# AT2560circuit.net
KiCad netlist of a schematic drawn in Altium Designer
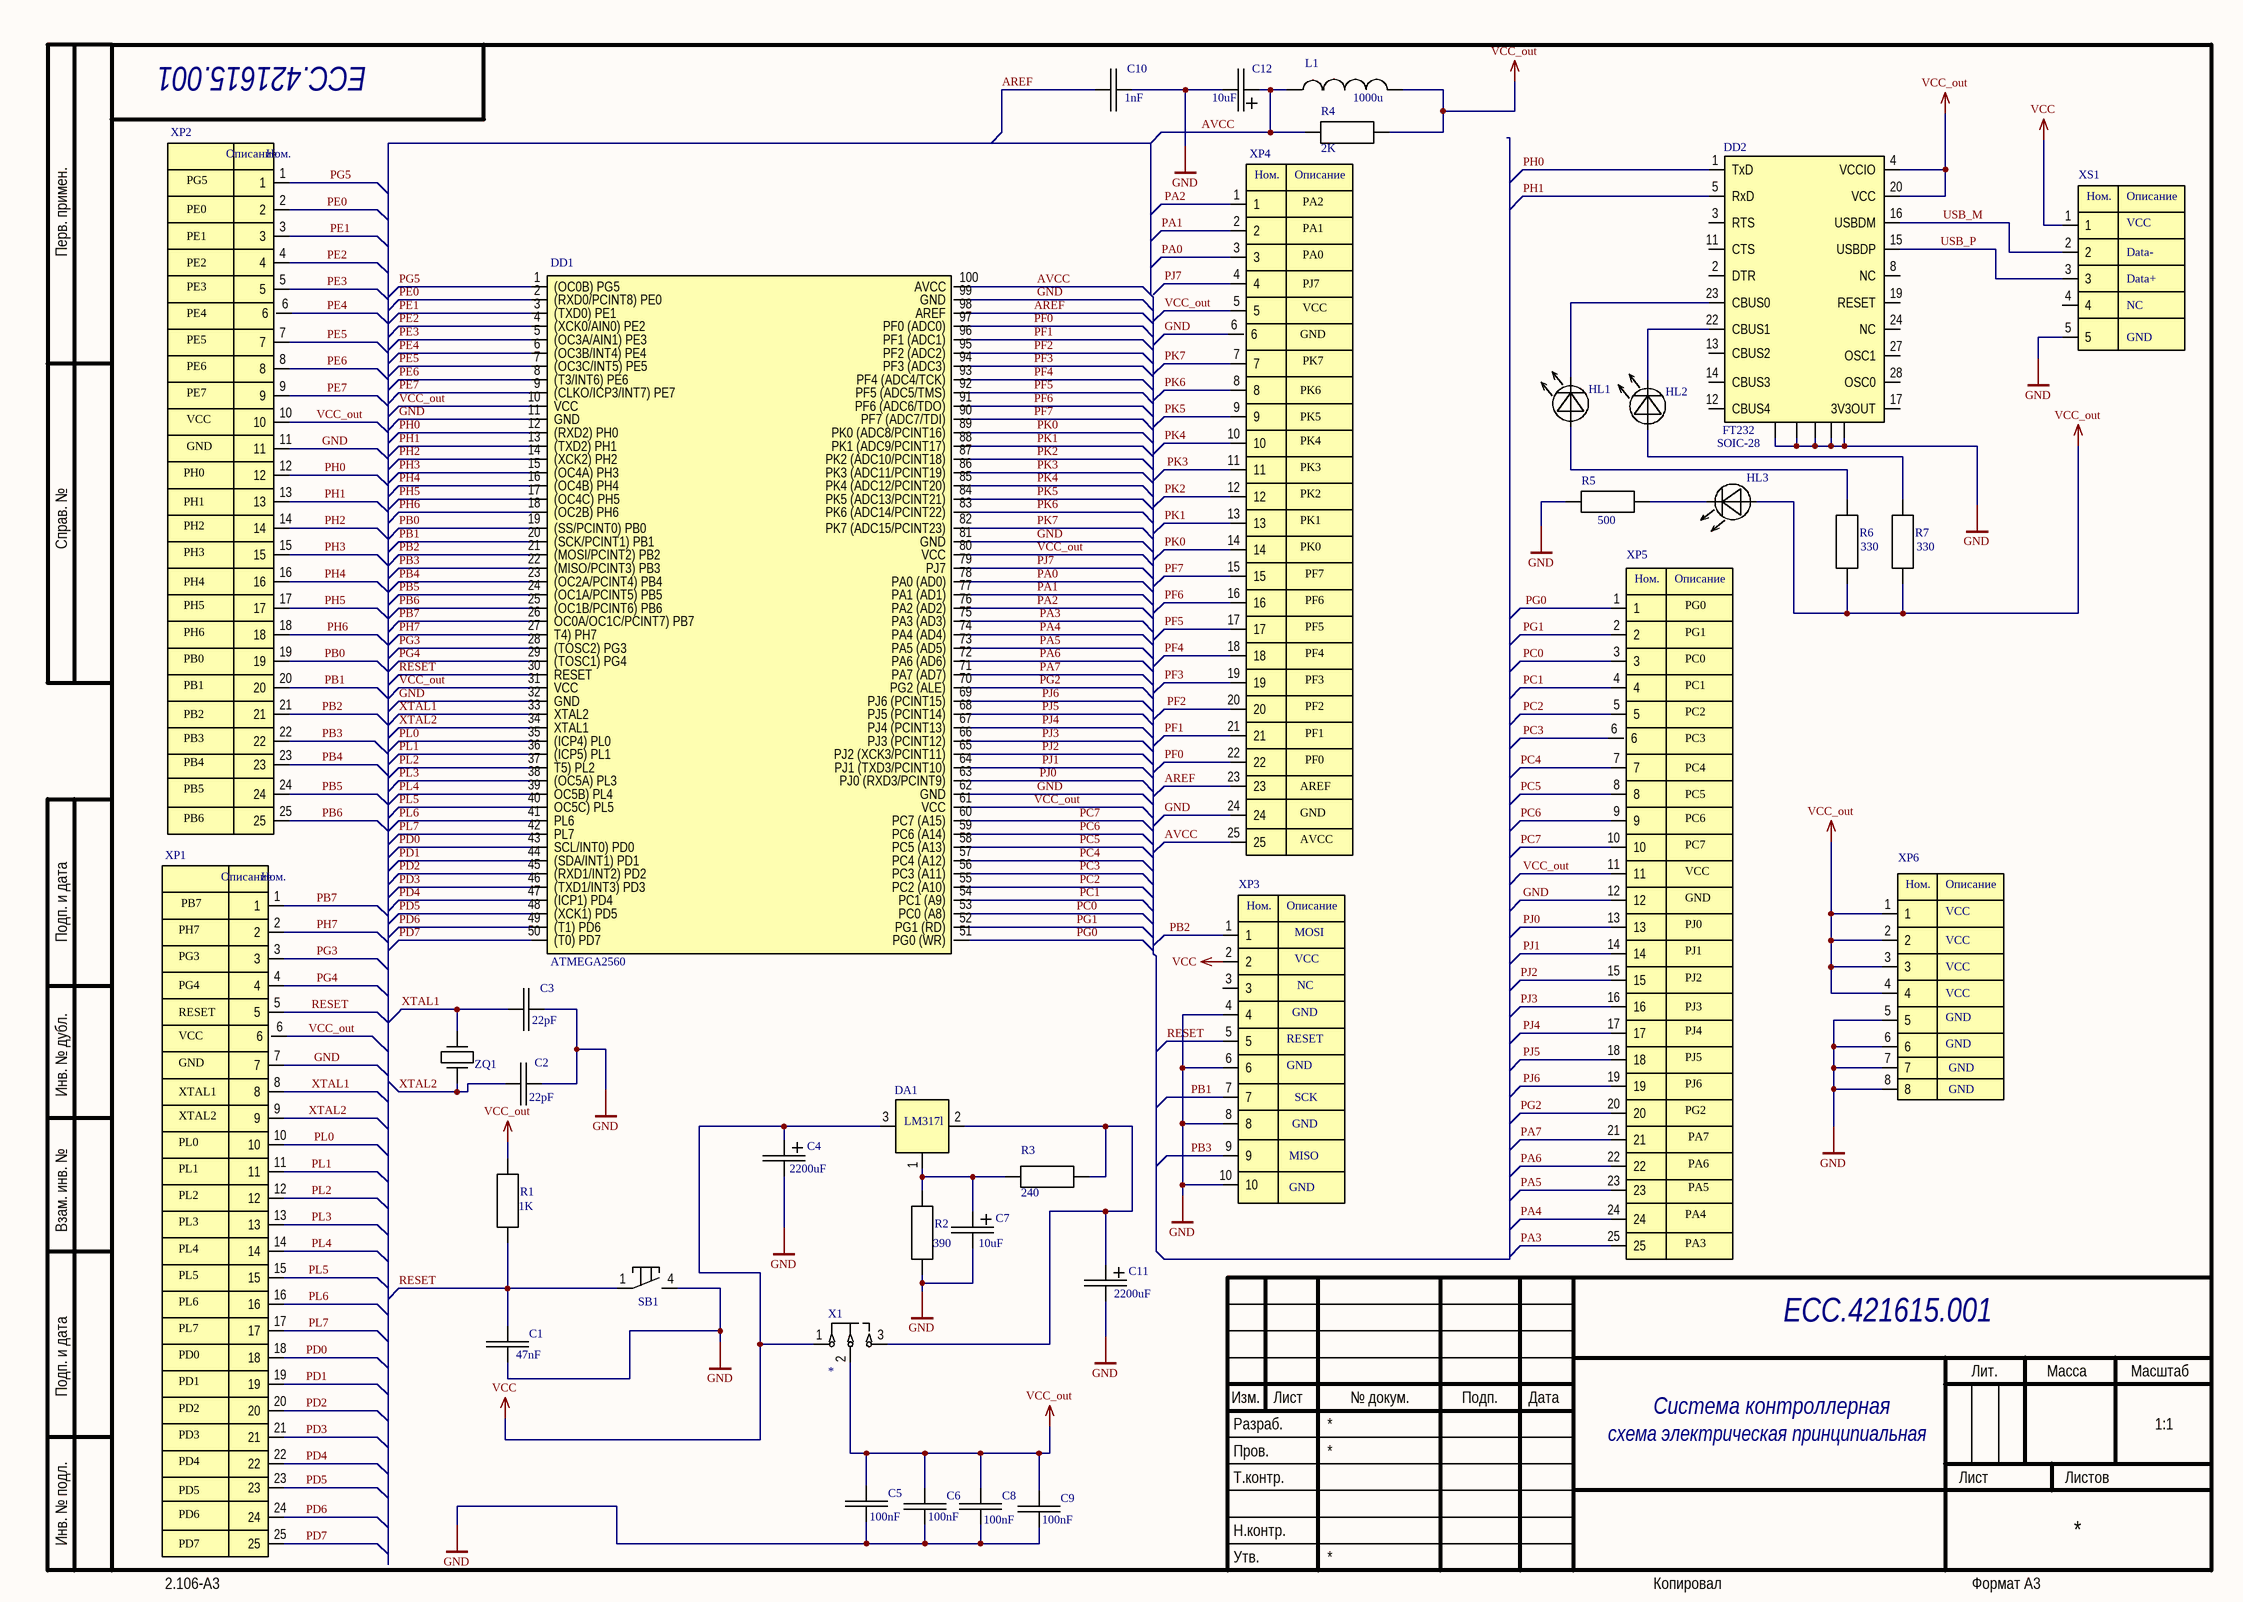
[diagram p0: AT2560circuit.SchDoc]

(export (version "E")
  (design (tool "Eeschema 10.0.6"))
  (components
    (comp (ref "C1")
      (value "Capasitor")
      (footprint "CAPC2012L")
      (fields (field (name "НОМИНАЛ") "47nF"))
      (libsource (lib "SchlibUGO") (part "Capasitor"))
    )
    (comp (ref "C2")
      (value "Capasitor")
      (footprint "CAPC2012L")
      (fields (field (name "НОМИНАЛ") "22pF"))
      (libsource (lib "SchlibUGO") (part "Capasitor"))
    )
    (comp (ref "C3")
      (value "Capasitor")
      (footprint "CAPC2012L")
      (fields (field (name "НОМИНАЛ") "22pF"))
      (libsource (lib "SchlibUGO") (part "Capasitor"))
    )
    (comp (ref "C4")
      (value "Electrolit_capasitor")
      (footprint "K50-Elect")
      (fields (field (name "НОМИНАЛ") "2200uF"))
      (libsource (lib "SchlibUGO") (part "Electrolit_capasitor"))
    )
    (comp (ref "C5")
      (value "Capasitor")
      (footprint "CAPC2012L")
      (fields (field (name "НОМИНАЛ") "100nF"))
      (libsource (lib "SchlibUGO") (part "Capasitor"))
    )
    (comp (ref "C6")
      (value "Capasitor")
      (footprint "CAPC2012L")
      (fields (field (name "НОМИНАЛ") "100nF"))
      (libsource (lib "SchlibUGO") (part "Capasitor"))
    )
    (comp (ref "C7")
      (value "Electrolit_capasitor")
      (footprint "K50-Elect")
      (fields (field (name "НОМИНАЛ") "10uF"))
      (libsource (lib "SchlibUGO") (part "Electrolit_capasitor"))
    )
    (comp (ref "C8")
      (value "Capasitor")
      (footprint "CAPC2012L")
      (fields (field (name "НОМИНАЛ") "100nF"))
      (libsource (lib "SchlibUGO") (part "Capasitor"))
    )
    (comp (ref "C9")
      (value "Capasitor")
      (footprint "CAPC2012L")
      (fields (field (name "НОМИНАЛ") "100nF"))
      (libsource (lib "SchlibUGO") (part "Capasitor"))
    )
    (comp (ref "C10")
      (value "Capasitor")
      (footprint "CAPC2012L")
      (fields (field (name "НОМИНАЛ") "1nF"))
      (libsource (lib "SchlibUGO") (part "Capasitor"))
    )
    (comp (ref "C11")
      (value "Electrolit_capasitor")
      (footprint "K50-Elect")
      (fields (field (name "НОМИНАЛ") "2200uF"))
      (libsource (lib "SchlibUGO") (part "Electrolit_capasitor"))
    )
    (comp (ref "C12")
      (value "Electrolit_capasitor")
      (footprint "K50-Elect")
      (fields (field (name "НОМИНАЛ") "10uF"))
      (libsource (lib "SchlibUGO") (part "Electrolit_capasitor"))
    )
    (comp (ref "DA1") (value "LM317l") (footprint "TO-263-3") (libsource (lib "SchlibUGO") (part "LM317l")))
    (comp (ref "DD1")
      (value "ATMega2560")
      (footprint "TSQFP50P1600X1600X120-100N")
      (fields (field (name "МАРКА") "ATMEGA2560"))
      (libsource (lib "SchlibUGO") (part "ATMega2560"))
    )
    (comp (ref "DD2")
      (value "FT232")
      (footprint "SSOP-28")
      (fields (field (name "МАРКА") "FT232") (field (name "КОРПУС") "SOIC-28"))
      (libsource (lib "SchlibUGO") (part "FT232"))
    )
    (comp (ref "HL1") (value "LED") (footprint "LED") (libsource (lib "SchlibUGO") (part "LED")))
    (comp (ref "HL2") (value "LED") (footprint "LED") (libsource (lib "SchlibUGO") (part "LED")))
    (comp (ref "HL3") (value "LED") (footprint "LED") (libsource (lib "SchlibUGO") (part "LED")))
    (comp (ref "L1")
      (value "Inductor")
      (footprint "Drossel")
      (fields (field (name "НОМИНАЛ") "1000u"))
      (libsource (lib "SchlibUGO") (part "Inductor"))
    )
    (comp (ref "R1")
      (value "Resistor")
      (footprint "RESC2012L")
      (fields (field (name "НОМИНАЛ") "1K"))
      (libsource (lib "SchlibUGO") (part "Resistor"))
    )
    (comp (ref "R2")
      (value "Resistor")
      (footprint "RESC2012L")
      (fields (field (name "НОМИНАЛ") "390"))
      (libsource (lib "SchlibUGO") (part "Resistor"))
    )
    (comp (ref "R3")
      (value "Resistor")
      (footprint "RESC2012L")
      (fields (field (name "НОМИНАЛ") "240"))
      (libsource (lib "SchlibUGO") (part "Resistor"))
    )
    (comp (ref "R4")
      (value "Resistor")
      (footprint "RESC2012L")
      (fields (field (name "НОМИНАЛ") "2K"))
      (libsource (lib "") (part "Resistor_1"))
    )
    (comp (ref "R5")
      (value "Resistor")
      (footprint "RESC2012L")
      (fields (field (name "НОМИНАЛ") "500"))
      (libsource (lib "SchlibUGO") (part "Resistor"))
    )
    (comp (ref "R6")
      (value "Resistor")
      (footprint "RESC2012L")
      (fields (field (name "НОМИНАЛ") "330"))
      (libsource (lib "SchlibUGO") (part "Resistor"))
    )
    (comp (ref "R7")
      (value "Resistor")
      (footprint "RESC2012L")
      (fields (field (name "НОМИНАЛ") "330"))
      (libsource (lib "SchlibUGO") (part "Resistor"))
    )
    (comp (ref "SB1") (value "button") (footprint "KLS2") (libsource (lib "SchlibUGO") (part "button")))
    (comp (ref "X1")
      (value "jumper")
      (footprint "PLSx3_XP")
      (fields (field (name "МАРКА") "*"))
      (libsource (lib "SchlibUGO") (part "jumper"))
    )
    (comp (ref "XP1")
      (value "Connector_plsx25")
      (footprint "PLSx25_XP")
      (libsource (lib "SchlibUGO") (part "Connector_plsx25"))
    )
    (comp (ref "XP2")
      (value "Connector_plsx25")
      (footprint "PLSx25_XP")
      (libsource (lib "") (part "Connector_plsx25_3"))
    )
    (comp (ref "XP3") (value "pls-6") (footprint "PLS6-2") (libsource (lib "SchlibUGO") (part "pls-6")))
    (comp (ref "XP4")
      (value "Connector_plsx25")
      (footprint "PLSx25_XP")
      (libsource (lib "") (part "Connector_plsx25_2"))
    )
    (comp (ref "XP5")
      (value "Connector_plsx25")
      (footprint "PLSx25_XP")
      (libsource (lib "") (part "Connector_plsx25_1"))
    )
    (comp (ref "XP6")
      (value "Power_Connector")
      (footprint "PLS-8-2")
      (libsource (lib "SchlibUGO") (part "Power_Connector"))
    )
    (comp (ref "XS1")
      (value "USB_mini_B")
      (footprint "KLS1-229-5FE")
      (libsource (lib "SchlibUGO") (part "USB_mini_B"))
    )
    (comp (ref "ZQ1") (value "Rezanator") (footprint "STS") (libsource (lib "SchlibUGO") (part "Rezanator")))
  )
  (nets
    (net (code "1") (name "/AREF") (class "Default")
      (node (ref "C10") (pin "1") (pinfunction "1_1") (pintype "passive"))
      (node (ref "DD1") (pin "98") (pinfunction "AREF_98") (pintype "passive"))
      (node (ref "XP4") (pin "23") (pinfunction "23_23") (pintype "passive"))
    )
    (net (code "2") (name "/AVCC") (class "Default")
      (node (ref "C12") (pin "1") (pinfunction "1_1") (pintype "passive"))
      (node (ref "DD1") (pin "100") (pinfunction "AVCC_100") (pintype "passive"))
      (node (ref "L1") (pin "1") (pinfunction "1_1") (pintype "passive"))
      (node (ref "R4") (pin "1") (pinfunction "1_1") (pintype "passive"))
      (node (ref "XP4") (pin "25") (pinfunction "25_25") (pintype "passive"))
    )
    (net (code "3") (name "/PA0") (class "Default")
      (node (ref "DD1") (pin "78") (pinfunction "PA0_(AD0)_78") (pintype "passive"))
      (node (ref "XP4") (pin "3") (pinfunction "3_3") (pintype "passive"))
    )
    (net (code "4") (name "/PA1") (class "Default")
      (node (ref "DD1") (pin "77") (pinfunction "PA1_(AD1)_77") (pintype "passive"))
      (node (ref "XP4") (pin "2") (pinfunction "2_2") (pintype "passive"))
    )
    (net (code "5") (name "/PA2") (class "Default")
      (node (ref "DD1") (pin "76") (pinfunction "PA2_(AD2)_76") (pintype "passive"))
      (node (ref "XP4") (pin "1") (pinfunction "1_1") (pintype "passive"))
    )
    (net (code "6") (name "/PA3") (class "Default")
      (node (ref "DD1") (pin "75") (pinfunction "PA3_(AD3)_75") (pintype "passive"))
      (node (ref "XP5") (pin "25") (pinfunction "25_25") (pintype "passive"))
    )
    (net (code "7") (name "/PA4") (class "Default")
      (node (ref "DD1") (pin "74") (pinfunction "PA4_(AD4)_74") (pintype "passive"))
      (node (ref "XP5") (pin "24") (pinfunction "24_24") (pintype "passive"))
    )
    (net (code "8") (name "/PA5") (class "Default")
      (node (ref "DD1") (pin "73") (pinfunction "PA5_(AD5)_73") (pintype "passive"))
      (node (ref "XP5") (pin "23") (pinfunction "23_23") (pintype "passive"))
    )
    (net (code "9") (name "/PA6") (class "Default")
      (node (ref "DD1") (pin "72") (pinfunction "PA6_(AD6)_72") (pintype "passive"))
      (node (ref "XP5") (pin "22") (pinfunction "22_22") (pintype "passive"))
    )
    (net (code "10") (name "/PA7") (class "Default")
      (node (ref "DD1") (pin "71") (pinfunction "PA7_(AD7)_71") (pintype "passive"))
      (node (ref "XP5") (pin "21") (pinfunction "21_21") (pintype "passive"))
    )
    (net (code "11") (name "/PB0") (class "Default")
      (node (ref "DD1") (pin "19") (pinfunction "(SS/PCINT0)_PB0_19") (pintype "passive"))
      (node (ref "XP2") (pin "19") (pinfunction "19_19") (pintype "passive"))
    )
    (net (code "12") (name "/PB1") (class "Default")
      (node (ref "DD1") (pin "20") (pinfunction "(SCK/PCINT1)_PB1_20") (pintype "passive"))
      (node (ref "XP2") (pin "20") (pinfunction "20_20") (pintype "passive"))
      (node (ref "XP3") (pin "7") (pinfunction "7_7") (pintype "passive"))
    )
    (net (code "13") (name "/PB2") (class "Default")
      (node (ref "DD1") (pin "21") (pinfunction "(MOSI/PCINT2)_PB2_21") (pintype "passive"))
      (node (ref "XP2") (pin "21") (pinfunction "21_21") (pintype "passive"))
      (node (ref "XP3") (pin "1") (pinfunction "1_1") (pintype "passive"))
    )
    (net (code "14") (name "/PB3") (class "Default")
      (node (ref "DD1") (pin "22") (pinfunction "(MISO/PCINT3)_PB3_22") (pintype "passive"))
      (node (ref "XP2") (pin "22") (pinfunction "22_22") (pintype "passive"))
      (node (ref "XP3") (pin "9") (pinfunction "9_9") (pintype "passive"))
    )
    (net (code "15") (name "/PB4") (class "Default")
      (node (ref "DD1") (pin "23") (pinfunction "(OC2A/PCINT4)_PB4_23") (pintype "passive"))
      (node (ref "XP2") (pin "23") (pinfunction "23_23") (pintype "passive"))
    )
    (net (code "16") (name "/PB5") (class "Default")
      (node (ref "DD1") (pin "24") (pinfunction "(OC1A/PCINT5)_PB5_24") (pintype "passive"))
      (node (ref "XP2") (pin "24") (pinfunction "24_24") (pintype "passive"))
    )
    (net (code "17") (name "/PB6") (class "Default")
      (node (ref "DD1") (pin "25") (pinfunction "(OC1B/PCINT6)_PB6_25") (pintype "passive"))
      (node (ref "XP2") (pin "25") (pinfunction "25_25") (pintype "passive"))
    )
    (net (code "18") (name "/PB7") (class "Default")
      (node (ref "DD1") (pin "26") (pinfunction "OC0A/OC1C/PCINT7)_PB7_26") (pintype "passive"))
      (node (ref "XP1") (pin "1") (pinfunction "1_1") (pintype "passive"))
    )
    (net (code "19") (name "/PC0") (class "Default")
      (node (ref "DD1") (pin "53") (pinfunction "PC0_(A8)_53") (pintype "passive"))
      (node (ref "XP5") (pin "3") (pinfunction "3_3") (pintype "passive"))
    )
    (net (code "20") (name "/PC1") (class "Default")
      (node (ref "DD1") (pin "54") (pinfunction "PC1_(A9)_54") (pintype "passive"))
      (node (ref "XP5") (pin "4") (pinfunction "4_4") (pintype "passive"))
    )
    (net (code "21") (name "/PC2") (class "Default")
      (node (ref "DD1") (pin "55") (pinfunction "PC2_(A10)_55") (pintype "passive"))
      (node (ref "XP5") (pin "5") (pinfunction "5_5") (pintype "passive"))
    )
    (net (code "22") (name "/PC3") (class "Default")
      (node (ref "DD1") (pin "56") (pinfunction "PC3_(A11)_56") (pintype "passive"))
      (node (ref "XP5") (pin "6") (pinfunction "6_6") (pintype "passive"))
    )
    (net (code "23") (name "/PC4") (class "Default")
      (node (ref "DD1") (pin "57") (pinfunction "PC4_(A12)_57") (pintype "passive"))
      (node (ref "XP5") (pin "7") (pinfunction "7_7") (pintype "passive"))
    )
    (net (code "24") (name "/PC5") (class "Default")
      (node (ref "DD1") (pin "58") (pinfunction "PC5_(A13)_58") (pintype "passive"))
      (node (ref "XP5") (pin "8") (pinfunction "8_8") (pintype "passive"))
    )
    (net (code "25") (name "/PC6") (class "Default")
      (node (ref "DD1") (pin "59") (pinfunction "PC6_(A14)_59") (pintype "passive"))
      (node (ref "XP5") (pin "9") (pinfunction "9_9") (pintype "passive"))
    )
    (net (code "26") (name "/PC7") (class "Default")
      (node (ref "DD1") (pin "60") (pinfunction "PC7_(A15)_60") (pintype "passive"))
      (node (ref "XP5") (pin "10") (pinfunction "10_10") (pintype "passive"))
    )
    (net (code "27") (name "/PD0") (class "Default")
      (node (ref "DD1") (pin "43") (pinfunction "SCL/INT0)_PD0_43") (pintype "passive"))
      (node (ref "XP1") (pin "18") (pinfunction "18_18") (pintype "passive"))
    )
    (net (code "28") (name "/PD1") (class "Default")
      (node (ref "DD1") (pin "44") (pinfunction "(SDA/INT1)_PD1_44") (pintype "passive"))
      (node (ref "XP1") (pin "19") (pinfunction "19_19") (pintype "passive"))
    )
    (net (code "29") (name "/PD2") (class "Default")
      (node (ref "DD1") (pin "45") (pinfunction "(RXD1/INT2)_PD2_45") (pintype "passive"))
      (node (ref "XP1") (pin "20") (pinfunction "20_20") (pintype "passive"))
    )
    (net (code "30") (name "/PD3") (class "Default")
      (node (ref "DD1") (pin "46") (pinfunction "(TXD1/INT3)_PD3_46") (pintype "passive"))
      (node (ref "XP1") (pin "21") (pinfunction "21_21") (pintype "passive"))
    )
    (net (code "31") (name "/PD4") (class "Default")
      (node (ref "DD1") (pin "47") (pinfunction "(ICP1)_PD4_47") (pintype "passive"))
      (node (ref "XP1") (pin "22") (pinfunction "22_22") (pintype "passive"))
    )
    (net (code "32") (name "/PD5") (class "Default")
      (node (ref "DD1") (pin "48") (pinfunction "(XCK1)_PD5_48") (pintype "passive"))
      (node (ref "XP1") (pin "23") (pinfunction "23_23") (pintype "passive"))
    )
    (net (code "33") (name "/PD6") (class "Default")
      (node (ref "DD1") (pin "49") (pinfunction "(T1)_PD6_49") (pintype "passive"))
      (node (ref "XP1") (pin "24") (pinfunction "24_24") (pintype "passive"))
    )
    (net (code "34") (name "/PD7") (class "Default")
      (node (ref "DD1") (pin "50") (pinfunction "(T0)_PD7_50") (pintype "passive"))
      (node (ref "XP1") (pin "25") (pinfunction "25_25") (pintype "passive"))
    )
    (net (code "35") (name "/PE0") (class "Default")
      (node (ref "DD1") (pin "2") (pinfunction "(RXD0/PCINT8)_PE0_2") (pintype "passive"))
      (node (ref "XP2") (pin "2") (pinfunction "2_2") (pintype "passive"))
    )
    (net (code "36") (name "/PE1") (class "Default")
      (node (ref "DD1") (pin "3") (pinfunction "(TXD0)_PE1_3") (pintype "passive"))
      (node (ref "XP2") (pin "3") (pinfunction "3_3") (pintype "passive"))
    )
    (net (code "37") (name "/PE2") (class "Default")
      (node (ref "DD1") (pin "4") (pinfunction "(XCK0/AIN0)_PE2_4") (pintype "passive"))
      (node (ref "XP2") (pin "4") (pinfunction "4_4") (pintype "passive"))
    )
    (net (code "38") (name "/PE3") (class "Default")
      (node (ref "DD1") (pin "5") (pinfunction "(OC3A/AIN1)_PE3_5") (pintype "passive"))
      (node (ref "XP2") (pin "5") (pinfunction "5_5") (pintype "passive"))
    )
    (net (code "39") (name "/PE4") (class "Default")
      (node (ref "DD1") (pin "6") (pinfunction "(OC3B/INT4)_PE4_6") (pintype "passive"))
      (node (ref "XP2") (pin "6") (pinfunction "6_6") (pintype "passive"))
    )
    (net (code "40") (name "/PE5") (class "Default")
      (node (ref "DD1") (pin "7") (pinfunction "(OC3C/INT5)_PE5_7") (pintype "passive"))
      (node (ref "XP2") (pin "7") (pinfunction "7_7") (pintype "passive"))
    )
    (net (code "41") (name "/PE6") (class "Default")
      (node (ref "DD1") (pin "8") (pinfunction "(T3/INT6)_PE6_8") (pintype "passive"))
      (node (ref "XP2") (pin "8") (pinfunction "8_8") (pintype "passive"))
    )
    (net (code "42") (name "/PE7") (class "Default")
      (node (ref "DD1") (pin "9") (pinfunction "(CLKO/ICP3/INT7)_PE7_9") (pintype "passive"))
      (node (ref "XP2") (pin "9") (pinfunction "9_9") (pintype "passive"))
    )
    (net (code "43") (name "/PF0") (class "Default")
      (node (ref "DD1") (pin "97") (pinfunction "PF0_(ADC0)_97") (pintype "passive"))
      (node (ref "XP4") (pin "22") (pinfunction "22_22") (pintype "passive"))
    )
    (net (code "44") (name "/PF1") (class "Default")
      (node (ref "DD1") (pin "96") (pinfunction "PF1_(ADC1)_96") (pintype "passive"))
      (node (ref "XP4") (pin "21") (pinfunction "21_21") (pintype "passive"))
    )
    (net (code "45") (name "/PF2") (class "Default")
      (node (ref "DD1") (pin "95") (pinfunction "PF2_(ADC2)_95") (pintype "passive"))
      (node (ref "XP4") (pin "20") (pinfunction "20_20") (pintype "passive"))
    )
    (net (code "46") (name "/PF3") (class "Default")
      (node (ref "DD1") (pin "94") (pinfunction "PF3_(ADC3)_94") (pintype "passive"))
      (node (ref "XP4") (pin "19") (pinfunction "19_19") (pintype "passive"))
    )
    (net (code "47") (name "/PF4") (class "Default")
      (node (ref "DD1") (pin "93") (pinfunction "PF4_(ADC4/TCK)_93") (pintype "passive"))
      (node (ref "XP4") (pin "18") (pinfunction "18_18") (pintype "passive"))
    )
    (net (code "48") (name "/PF5") (class "Default")
      (node (ref "DD1") (pin "92") (pinfunction "PF5_(ADC5/TMS)_92") (pintype "passive"))
      (node (ref "XP4") (pin "17") (pinfunction "17_17") (pintype "passive"))
    )
    (net (code "49") (name "/PF6") (class "Default")
      (node (ref "DD1") (pin "91") (pinfunction "PF6_(ADC6/TDO)_91") (pintype "passive"))
      (node (ref "XP4") (pin "16") (pinfunction "16_16") (pintype "passive"))
    )
    (net (code "50") (name "/PF7") (class "Default")
      (node (ref "DD1") (pin "90") (pinfunction "PF7_(ADC7/TDI)_90") (pintype "passive"))
      (node (ref "XP4") (pin "15") (pinfunction "15_15") (pintype "passive"))
    )
    (net (code "51") (name "/PG0") (class "Default")
      (node (ref "DD1") (pin "51") (pinfunction "PG0_(WR)_51") (pintype "passive"))
      (node (ref "XP5") (pin "1") (pinfunction "1_1") (pintype "passive"))
    )
    (net (code "52") (name "/PG1") (class "Default")
      (node (ref "DD1") (pin "52") (pinfunction "PG1_(RD)_52") (pintype "passive"))
      (node (ref "XP5") (pin "2") (pinfunction "2_2") (pintype "passive"))
    )
    (net (code "53") (name "/PG2") (class "Default")
      (node (ref "DD1") (pin "70") (pinfunction "PG2_(ALE)_70") (pintype "passive"))
      (node (ref "XP5") (pin "20") (pinfunction "20_20") (pintype "passive"))
    )
    (net (code "54") (name "/PG3") (class "Default")
      (node (ref "DD1") (pin "28") (pinfunction "(TOSC2)_PG3_28") (pintype "passive"))
      (node (ref "XP1") (pin "3") (pinfunction "3_3") (pintype "passive"))
    )
    (net (code "55") (name "/PG4") (class "Default")
      (node (ref "DD1") (pin "29") (pinfunction "(TOSC1)_PG4_29") (pintype "passive"))
      (node (ref "XP1") (pin "4") (pinfunction "4_4") (pintype "passive"))
    )
    (net (code "56") (name "/PG5") (class "Default")
      (node (ref "DD1") (pin "1") (pinfunction "(OC0B)_PG5_1") (pintype "passive"))
      (node (ref "XP2") (pin "1") (pinfunction "1_1") (pintype "passive"))
    )
    (net (code "57") (name "/PH0") (class "Default")
      (node (ref "DD1") (pin "12") (pinfunction "(RXD2)_PH0_12") (pintype "passive"))
      (node (ref "DD2") (pin "1") (pinfunction "TxD_1") (pintype "passive"))
      (node (ref "XP2") (pin "12") (pinfunction "12_12") (pintype "passive"))
    )
    (net (code "58") (name "/PH1") (class "Default")
      (node (ref "DD1") (pin "13") (pinfunction "(TXD2)_PH1_13") (pintype "passive"))
      (node (ref "DD2") (pin "5") (pinfunction "RxD_5") (pintype "passive"))
      (node (ref "XP2") (pin "13") (pinfunction "13_13") (pintype "passive"))
    )
    (net (code "59") (name "/PH2") (class "Default")
      (node (ref "DD1") (pin "14") (pinfunction "(XCK2)_PH2_14") (pintype "passive"))
      (node (ref "XP2") (pin "14") (pinfunction "14_14") (pintype "passive"))
    )
    (net (code "60") (name "/PH3") (class "Default")
      (node (ref "DD1") (pin "15") (pinfunction "(OC4A)_PH3_15") (pintype "passive"))
      (node (ref "XP2") (pin "15") (pinfunction "15_15") (pintype "passive"))
    )
    (net (code "61") (name "/PH4") (class "Default")
      (node (ref "DD1") (pin "16") (pinfunction "(OC4B)_PH4_16") (pintype "passive"))
      (node (ref "XP2") (pin "16") (pinfunction "16_16") (pintype "passive"))
    )
    (net (code "62") (name "/PH5") (class "Default")
      (node (ref "DD1") (pin "17") (pinfunction "(OC4C)_PH5_17") (pintype "passive"))
      (node (ref "XP2") (pin "17") (pinfunction "17_17") (pintype "passive"))
    )
    (net (code "63") (name "/PH6") (class "Default")
      (node (ref "DD1") (pin "18") (pinfunction "(OC2B)_PH6_18") (pintype "passive"))
      (node (ref "XP2") (pin "18") (pinfunction "18_18") (pintype "passive"))
    )
    (net (code "64") (name "/PH7") (class "Default")
      (node (ref "DD1") (pin "27") (pinfunction "T4)_PH7_27") (pintype "passive"))
      (node (ref "XP1") (pin "2") (pinfunction "2_2") (pintype "passive"))
    )
    (net (code "65") (name "/PJ0") (class "Default")
      (node (ref "DD1") (pin "63") (pinfunction "PJ0_(RXD3/PCINT9)_63") (pintype "passive"))
      (node (ref "XP5") (pin "13") (pinfunction "13_13") (pintype "passive"))
    )
    (net (code "66") (name "/PJ1") (class "Default")
      (node (ref "DD1") (pin "64") (pinfunction "PJ1_(TXD3/PCINT10)_64") (pintype "passive"))
      (node (ref "XP5") (pin "14") (pinfunction "14_14") (pintype "passive"))
    )
    (net (code "67") (name "/PJ2") (class "Default")
      (node (ref "DD1") (pin "65") (pinfunction "PJ2_(XCK3/PCINT11)_65") (pintype "passive"))
      (node (ref "XP5") (pin "15") (pinfunction "15_15") (pintype "passive"))
    )
    (net (code "68") (name "/PJ3") (class "Default")
      (node (ref "DD1") (pin "66") (pinfunction "PJ3_(PCINT12)_66") (pintype "passive"))
      (node (ref "XP5") (pin "16") (pinfunction "16_16") (pintype "passive"))
    )
    (net (code "69") (name "/PJ4") (class "Default")
      (node (ref "DD1") (pin "67") (pinfunction "PJ4_(PCINT13)_67") (pintype "passive"))
      (node (ref "XP5") (pin "17") (pinfunction "17_17") (pintype "passive"))
    )
    (net (code "70") (name "/PJ5") (class "Default")
      (node (ref "DD1") (pin "68") (pinfunction "PJ5_(PCINT14)_68") (pintype "passive"))
      (node (ref "XP5") (pin "18") (pinfunction "18_18") (pintype "passive"))
    )
    (net (code "71") (name "/PJ6") (class "Default")
      (node (ref "DD1") (pin "69") (pinfunction "PJ6_(PCINT15)_69") (pintype "passive"))
      (node (ref "XP5") (pin "19") (pinfunction "19_19") (pintype "passive"))
    )
    (net (code "72") (name "/PJ7") (class "Default")
      (node (ref "DD1") (pin "79") (pinfunction "PJ7_79") (pintype "passive"))
      (node (ref "XP4") (pin "4") (pinfunction "4_4") (pintype "passive"))
    )
    (net (code "73") (name "/PK0") (class "Default")
      (node (ref "DD1") (pin "89") (pinfunction "PK0_(ADC8/PCINT16)_89") (pintype "passive"))
      (node (ref "XP4") (pin "14") (pinfunction "14_14") (pintype "passive"))
    )
    (net (code "74") (name "/PK1") (class "Default")
      (node (ref "DD1") (pin "88") (pinfunction "PK1_(ADC9/PCINT17)_88") (pintype "passive"))
      (node (ref "XP4") (pin "13") (pinfunction "13_13") (pintype "passive"))
    )
    (net (code "75") (name "/PK2") (class "Default")
      (node (ref "DD1") (pin "87") (pinfunction "PK2_(ADC10/PCINT18)_87") (pintype "passive"))
      (node (ref "XP4") (pin "12") (pinfunction "12_12") (pintype "passive"))
    )
    (net (code "76") (name "/PK3") (class "Default")
      (node (ref "DD1") (pin "86") (pinfunction "PK3_(ADC11/PCINT19)_86") (pintype "passive"))
      (node (ref "XP4") (pin "11") (pinfunction "11_11") (pintype "passive"))
    )
    (net (code "77") (name "/PK4") (class "Default")
      (node (ref "DD1") (pin "85") (pinfunction "PK4_(ADC12/PCINT20)_85") (pintype "passive"))
      (node (ref "XP4") (pin "10") (pinfunction "10_10") (pintype "passive"))
    )
    (net (code "78") (name "/PK5") (class "Default")
      (node (ref "DD1") (pin "84") (pinfunction "PK5_(ADC13/PCINT21)_84") (pintype "passive"))
      (node (ref "XP4") (pin "9") (pinfunction "9_9") (pintype "passive"))
    )
    (net (code "79") (name "/PK6") (class "Default")
      (node (ref "DD1") (pin "83") (pinfunction "PK6_(ADC14/PCINT22)_83") (pintype "passive"))
      (node (ref "XP4") (pin "8") (pinfunction "8_8") (pintype "passive"))
    )
    (net (code "80") (name "/PK7") (class "Default")
      (node (ref "DD1") (pin "82") (pinfunction "PK7_(ADC15/PCINT23)_82") (pintype "passive"))
      (node (ref "XP4") (pin "7") (pinfunction "7_7") (pintype "passive"))
    )
    (net (code "81") (name "/PL0") (class "Default")
      (node (ref "DD1") (pin "35") (pinfunction "(ICP4)_PL0_35") (pintype "passive"))
      (node (ref "XP1") (pin "10") (pinfunction "10_10") (pintype "passive"))
    )
    (net (code "82") (name "/PL1") (class "Default")
      (node (ref "DD1") (pin "36") (pinfunction "(ICP5)_PL1_36") (pintype "passive"))
      (node (ref "XP1") (pin "11") (pinfunction "11_11") (pintype "passive"))
    )
    (net (code "83") (name "/PL2") (class "Default")
      (node (ref "DD1") (pin "37") (pinfunction "T5)_PL2_37") (pintype "passive"))
      (node (ref "XP1") (pin "12") (pinfunction "12_12") (pintype "passive"))
    )
    (net (code "84") (name "/PL3") (class "Default")
      (node (ref "DD1") (pin "38") (pinfunction "(OC5A)_PL3_38") (pintype "passive"))
      (node (ref "XP1") (pin "13") (pinfunction "13_13") (pintype "passive"))
    )
    (net (code "85") (name "/PL4") (class "Default")
      (node (ref "DD1") (pin "39") (pinfunction "OC5B)_PL4_39") (pintype "passive"))
      (node (ref "XP1") (pin "14") (pinfunction "14_14") (pintype "passive"))
    )
    (net (code "86") (name "/PL5") (class "Default")
      (node (ref "DD1") (pin "40") (pinfunction "OC5C)_PL5_40") (pintype "passive"))
      (node (ref "XP1") (pin "15") (pinfunction "15_15") (pintype "passive"))
    )
    (net (code "87") (name "/PL6") (class "Default")
      (node (ref "DD1") (pin "41") (pinfunction "PL6_41") (pintype "passive"))
      (node (ref "XP1") (pin "16") (pinfunction "16_16") (pintype "passive"))
    )
    (net (code "88") (name "/PL7") (class "Default")
      (node (ref "DD1") (pin "42") (pinfunction "PL7_42") (pintype "passive"))
      (node (ref "XP1") (pin "17") (pinfunction "17_17") (pintype "passive"))
    )
    (net (code "89") (name "/RESET") (class "Default")
      (node (ref "C1") (pin "1") (pinfunction "1_1") (pintype "passive"))
      (node (ref "DD1") (pin "30") (pinfunction "RESET_30") (pintype "passive"))
      (node (ref "R1") (pin "1") (pinfunction "1_1") (pintype "passive"))
      (node (ref "SB1") (pin "1") (pinfunction "1_1") (pintype "passive"))
      (node (ref "XP1") (pin "5") (pinfunction "5_5") (pintype "passive"))
      (node (ref "XP3") (pin "5") (pinfunction "5_5") (pintype "passive"))
    )
    (net (code "90") (name "/USB_M") (class "Default")
      (node (ref "DD2") (pin "16") (pinfunction "USBDM_16") (pintype "passive"))
      (node (ref "XS1") (pin "2") (pinfunction "2_2") (pintype "passive"))
    )
    (net (code "91") (name "/USB_P") (class "Default")
      (node (ref "DD2") (pin "15") (pinfunction "USBDP_15") (pintype "passive"))
      (node (ref "XS1") (pin "3") (pinfunction "3_3") (pintype "passive"))
    )
    (net (code "92") (name "/XTAL1") (class "Default")
      (node (ref "C3") (pin "2") (pinfunction "2_2") (pintype "passive"))
      (node (ref "DD1") (pin "33") (pinfunction "XTAL2_33") (pintype "passive"))
      (node (ref "XP1") (pin "8") (pinfunction "8_8") (pintype "passive"))
      (node (ref "ZQ1") (pin "2") (pinfunction "2_2") (pintype "passive"))
    )
    (net (code "93") (name "/XTAL2") (class "Default")
      (node (ref "C2") (pin "2") (pinfunction "2_2") (pintype "passive"))
      (node (ref "DD1") (pin "34") (pinfunction "XTAL1_34") (pintype "passive"))
      (node (ref "XP1") (pin "9") (pinfunction "9_9") (pintype "passive"))
      (node (ref "ZQ1") (pin "1") (pinfunction "1_1") (pintype "passive"))
    )
    (net (code "94") (name "GND") (class "Default")
      (node (ref "C1") (pin "2") (pinfunction "2_2") (pintype "passive"))
      (node (ref "C10") (pin "2") (pinfunction "2_2") (pintype "passive"))
      (node (ref "C11") (pin "2") (pinfunction "2_2") (pintype "passive"))
      (node (ref "C12") (pin "2") (pinfunction "2_2") (pintype "passive"))
      (node (ref "C2") (pin "1") (pinfunction "1_1") (pintype "passive"))
      (node (ref "C3") (pin "1") (pinfunction "1_1") (pintype "passive"))
      (node (ref "C4") (pin "2") (pinfunction "2_2") (pintype "passive"))
      (node (ref "C5") (pin "2") (pinfunction "2_2") (pintype "passive"))
      (node (ref "C6") (pin "2") (pinfunction "2_2") (pintype "passive"))
      (node (ref "C7") (pin "2") (pinfunction "2_2") (pintype "passive"))
      (node (ref "C8") (pin "2") (pinfunction "2_2") (pintype "passive"))
      (node (ref "C9") (pin "2") (pinfunction "2_2") (pintype "passive"))
      (node (ref "DD1") (pin "11") (pinfunction "GND_11") (pintype "passive"))
      (node (ref "DD1") (pin "32") (pinfunction "GND_32") (pintype "passive"))
      (node (ref "DD1") (pin "62") (pinfunction "GND_62") (pintype "passive"))
      (node (ref "DD1") (pin "81") (pinfunction "GND_81") (pintype "passive"))
      (node (ref "DD1") (pin "99") (pinfunction "GND_99") (pintype "passive"))
      (node (ref "DD2") (pin "18") (pinfunction "18_18") (pintype "passive"))
      (node (ref "DD2") (pin "21") (pinfunction "21_21") (pintype "passive"))
      (node (ref "DD2") (pin "25") (pinfunction "25_25") (pintype "passive"))
      (node (ref "DD2") (pin "26") (pinfunction "26_26") (pintype "passive"))
      (node (ref "DD2") (pin "7") (pinfunction "7_7") (pintype "passive"))
      (node (ref "R2") (pin "1") (pinfunction "1_1") (pintype "passive"))
      (node (ref "R5") (pin "1") (pinfunction "1_1") (pintype "passive"))
      (node (ref "SB1") (pin "4") (pinfunction "4_4") (pintype "passive"))
      (node (ref "XP1") (pin "7") (pinfunction "7_7") (pintype "passive"))
      (node (ref "XP2") (pin "11") (pinfunction "11_11") (pintype "passive"))
      (node (ref "XP3") (pin "10") (pinfunction "10_10") (pintype "passive"))
      (node (ref "XP3") (pin "4") (pinfunction "4_4") (pintype "passive"))
      (node (ref "XP3") (pin "6") (pinfunction "6_6") (pintype "passive"))
      (node (ref "XP3") (pin "8") (pinfunction "8_8") (pintype "passive"))
      (node (ref "XP4") (pin "24") (pinfunction "24_24") (pintype "passive"))
      (node (ref "XP4") (pin "6") (pinfunction "6_6") (pintype "passive"))
      (node (ref "XP5") (pin "12") (pinfunction "12_12") (pintype "passive"))
      (node (ref "XP6") (pin "5") (pinfunction "5_5") (pintype "passive"))
      (node (ref "XP6") (pin "6") (pinfunction "6_6") (pintype "passive"))
      (node (ref "XP6") (pin "7") (pinfunction "7_7") (pintype "passive"))
      (node (ref "XP6") (pin "8") (pinfunction "8_8") (pintype "passive"))
      (node (ref "XS1") (pin "5") (pinfunction "5_5") (pintype "passive"))
    )
    (net (code "95") (name "Net-(C7-Pad1)") (class "Default")
      (node (ref "C7") (pin "1") (pinfunction "1_1") (pintype "passive"))
      (node (ref "DA1") (pin "1") (pinfunction "1_1") (pintype "passive"))
      (node (ref "R2") (pin "2") (pinfunction "2_2") (pintype "passive"))
      (node (ref "R3") (pin "2") (pinfunction "2_2") (pintype "passive"))
    )
    (net (code "96") (name "Net-(C11-Pad1)") (class "Default")
      (node (ref "C11") (pin "1") (pinfunction "1_1") (pintype "passive"))
      (node (ref "DA1") (pin "2") (pinfunction "2_2") (pintype "passive"))
      (node (ref "R3") (pin "1") (pinfunction "1_1") (pintype "passive"))
      (node (ref "X1") (pin "3") (pinfunction "3_3") (pintype "passive"))
    )
    (net (code "97") (name "Net-(DD2-CBUS0)") (class "Default")
      (node (ref "DD2") (pin "23") (pinfunction "CBUS0_23") (pintype "passive"))
      (node (ref "HL1") (pin "2") (pinfunction "2_2") (pintype "passive"))
    )
    (net (code "98") (name "Net-(DD2-CBUS1)") (class "Default")
      (node (ref "DD2") (pin "22") (pinfunction "CBUS1_22") (pintype "passive"))
      (node (ref "HL2") (pin "2") (pinfunction "2_2") (pintype "passive"))
    )
    (net (code "99") (name "Net-(HL1-Pad1)") (class "Default")
      (node (ref "HL1") (pin "1") (pinfunction "1_1") (pintype "passive"))
      (node (ref "R6") (pin "2") (pinfunction "2_2") (pintype "passive"))
    )
    (net (code "100") (name "Net-(HL2-Pad1)") (class "Default")
      (node (ref "HL2") (pin "1") (pinfunction "1_1") (pintype "passive"))
      (node (ref "R7") (pin "2") (pinfunction "2_2") (pintype "passive"))
    )
    (net (code "101") (name "Net-(HL3-Pad2)") (class "Default")
      (node (ref "HL3") (pin "2") (pinfunction "2_2") (pintype "passive"))
      (node (ref "R5") (pin "2") (pinfunction "2_2") (pintype "passive"))
    )
    (net (code "102") (name "VCC") (class "Default")
      (node (ref "C4") (pin "1") (pinfunction "1_1") (pintype "passive"))
      (node (ref "DA1") (pin "3") (pinfunction "3_3") (pintype "passive"))
      (node (ref "X1") (pin "1") (pinfunction "1_1") (pintype "passive"))
      (node (ref "XP3") (pin "2") (pinfunction "2_2") (pintype "passive"))
      (node (ref "XS1") (pin "1") (pinfunction "1_1") (pintype "passive"))
    )
    (net (code "103") (name "VCC_out") (class "Default")
      (node (ref "C5") (pin "1") (pinfunction "1_1") (pintype "passive"))
      (node (ref "C6") (pin "1") (pinfunction "1_1") (pintype "passive"))
      (node (ref "C8") (pin "1") (pinfunction "1_1") (pintype "passive"))
      (node (ref "C9") (pin "1") (pinfunction "1_1") (pintype "passive"))
      (node (ref "DD1") (pin "10") (pinfunction "VCC_10") (pintype "passive"))
      (node (ref "DD1") (pin "31") (pinfunction "VCC_31") (pintype "passive"))
      (node (ref "DD1") (pin "61") (pinfunction "VCC_61") (pintype "passive"))
      (node (ref "DD1") (pin "80") (pinfunction "VCC_80") (pintype "passive"))
      (node (ref "DD2") (pin "20") (pinfunction "VCC_20") (pintype "passive"))
      (node (ref "DD2") (pin "4") (pinfunction "VCCIO_4") (pintype "passive"))
      (node (ref "HL3") (pin "1") (pinfunction "1_1") (pintype "passive"))
      (node (ref "L1") (pin "2") (pinfunction "2_2") (pintype "passive"))
      (node (ref "R1") (pin "2") (pinfunction "2_2") (pintype "passive"))
      (node (ref "R4") (pin "2") (pinfunction "2_2") (pintype "passive"))
      (node (ref "R6") (pin "1") (pinfunction "1_1") (pintype "passive"))
      (node (ref "R7") (pin "1") (pinfunction "1_1") (pintype "passive"))
      (node (ref "X1") (pin "2") (pinfunction "2_2") (pintype "passive"))
      (node (ref "XP1") (pin "6") (pinfunction "6_6") (pintype "passive"))
      (node (ref "XP2") (pin "10") (pinfunction "10_10") (pintype "passive"))
      (node (ref "XP4") (pin "5") (pinfunction "5_5") (pintype "passive"))
      (node (ref "XP5") (pin "11") (pinfunction "11_11") (pintype "passive"))
      (node (ref "XP6") (pin "1") (pinfunction "1_1") (pintype "passive"))
      (node (ref "XP6") (pin "2") (pinfunction "2_2") (pintype "passive"))
      (node (ref "XP6") (pin "3") (pinfunction "3_3") (pintype "passive"))
      (node (ref "XP6") (pin "4") (pinfunction "4_4") (pintype "passive"))
    )
    (net (code "104") (name "unconnected-(DD2-3V3OUT-Pad17)") (class "Default")
      (node (ref "DD2") (pin "17") (pinfunction "3V3OUT_17") (pintype "passive"))
    )
    (net (code "105") (name "unconnected-(DD2-CBUS2-Pad13)") (class "Default")
      (node (ref "DD2") (pin "13") (pinfunction "CBUS2_13") (pintype "passive"))
    )
    (net (code "106") (name "unconnected-(DD2-CBUS3-Pad14)") (class "Default")
      (node (ref "DD2") (pin "14") (pinfunction "CBUS3_14") (pintype "passive"))
    )
    (net (code "107") (name "unconnected-(DD2-CBUS4-Pad12)") (class "Default")
      (node (ref "DD2") (pin "12") (pinfunction "CBUS4_12") (pintype "passive"))
    )
    (net (code "108") (name "unconnected-(DD2-CTS-Pad11)") (class "Default")
      (node (ref "DD2") (pin "11") (pinfunction "CTS_11") (pintype "passive"))
    )
    (net (code "109") (name "unconnected-(DD2-DTR-Pad2)") (class "Default")
      (node (ref "DD2") (pin "2") (pinfunction "DTR_2") (pintype "passive"))
    )
    (net (code "110") (name "unconnected-(DD2-NC-Pad8)") (class "Default")
      (node (ref "DD2") (pin "8") (pinfunction "NC_8") (pintype "passive"))
    )
    (net (code "111") (name "unconnected-(DD2-NC-Pad24)") (class "Default")
      (node (ref "DD2") (pin "24") (pinfunction "NC_24") (pintype "passive"))
    )
    (net (code "112") (name "unconnected-(DD2-OSC0-Pad28)") (class "Default")
      (node (ref "DD2") (pin "28") (pinfunction "OSC0_28") (pintype "passive"))
    )
    (net (code "113") (name "unconnected-(DD2-OSC1-Pad27)") (class "Default")
      (node (ref "DD2") (pin "27") (pinfunction "OSC1_27") (pintype "passive"))
    )
    (net (code "114") (name "unconnected-(DD2-RESET-Pad19)") (class "Default")
      (node (ref "DD2") (pin "19") (pinfunction "RESET_19") (pintype "passive"))
    )
    (net (code "115") (name "unconnected-(DD2-RTS-Pad3)") (class "Default")
      (node (ref "DD2") (pin "3") (pinfunction "RTS_3") (pintype "passive"))
    )
    (net (code "116") (name "unconnected-(XP3-Pad3)") (class "Default")
      (node (ref "XP3") (pin "3") (pinfunction "3_3") (pintype "passive"))
    )
    (net (code "117") (name "unconnected-(XS1-Pad4)") (class "Default")
      (node (ref "XS1") (pin "4") (pinfunction "4_4") (pintype "passive"))
    )
  )
)
